# VOICE.net
KiCad netlist of a schematic drawn in Altium Designer
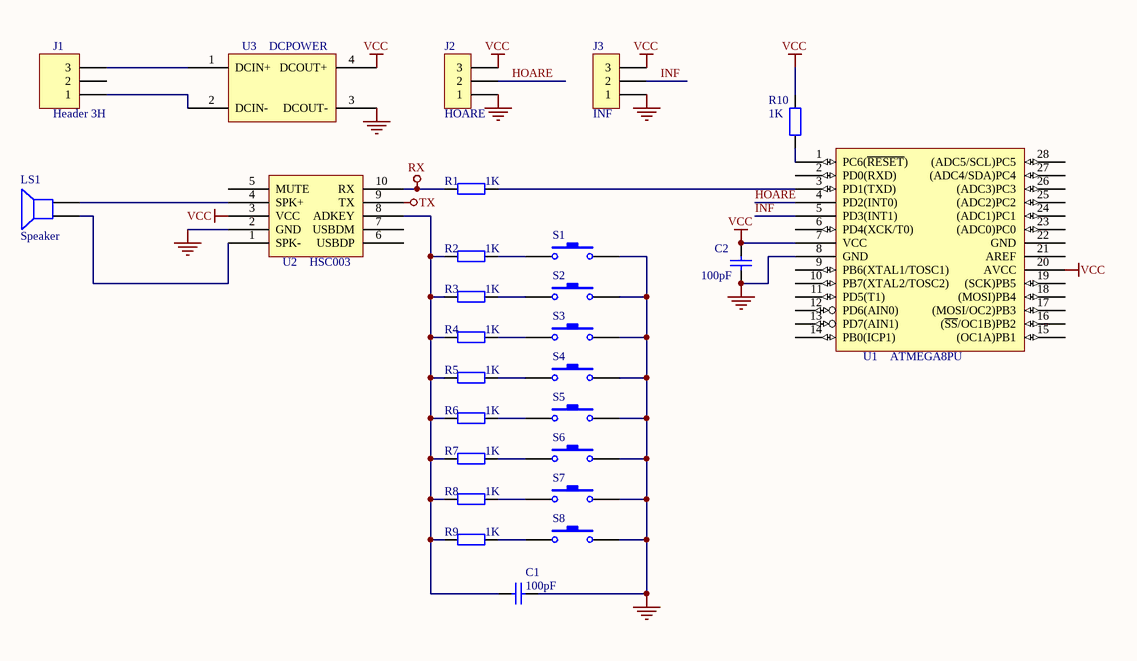
[diagram p0: VOICE.SchDoc]

(export (version "E")
  (design (tool "Eeschema 10.0.6"))
  (components
    (comp (ref "C1")
      (value "100pF")
      (footprint "RAD-0.3")
      (description "Capacitor")
      (fields (field (name "Comment") "CAP") (field (name "PUBLISHER") "Altium Limited"))
      (libsource (lib "Miscellaneous Devices") (part "Cap"))
    )
    (comp (ref "C2")
      (value "100pF")
      (footprint "RAD-0.3")
      (description "Capacitor")
      (fields (field (name "Comment") "CAP") (field (name "PUBLISHER") "Altium Limited"))
      (libsource (lib "Miscellaneous Devices") (part "Cap"))
    )
    (comp (ref "J1")
      (value "Header 3H")
      (footprint "HDR1X3H")
      (description "Header, 3-Pin, Right Angle")
      (fields (field (name "PUBLISHER") "Altium Limited"))
      (libsource (lib "Miscellaneous Connectors") (part "Header 3H"))
    )
    (comp (ref "J2") (value "HOARE") (description "Connector") (libsource (lib "*") (part "CON3")))
    (comp (ref "J3") (value "INF") (description "Connector") (libsource (lib "*") (part "CON3")))
    (comp (ref "LS1")
      (value "Speaker")
      (footprint "PIN2")
      (description "Loudspeaker")
      (fields (field (name "PUBLISHER") "Altium Limited"))
      (libsource (lib "Miscellaneous Devices") (part "Speaker"))
    )
    (comp (ref "R1")
      (value "1K")
      (footprint "AXIAL-0.4")
      (description "Resistor")
      (fields (field (name "Comment") "RES2") (field (name "PUBLISHER") "Altium Limited"))
      (libsource (lib "") (part "Res2_1"))
    )
    (comp (ref "R2")
      (value "1K")
      (footprint "AXIAL-0.4")
      (description "Resistor")
      (fields (field (name "Comment") "RES2") (field (name "PUBLISHER") "Altium Limited"))
      (libsource (lib "") (part "Res2_1"))
    )
    (comp (ref "R3")
      (value "1K")
      (footprint "AXIAL-0.4")
      (description "Resistor")
      (fields (field (name "Comment") "RES2") (field (name "PUBLISHER") "Altium Limited"))
      (libsource (lib "") (part "Res2_1"))
    )
    (comp (ref "R4")
      (value "1K")
      (footprint "AXIAL-0.4")
      (description "Resistor")
      (fields (field (name "Comment") "RES2") (field (name "PUBLISHER") "Altium Limited"))
      (libsource (lib "") (part "Res2_1"))
    )
    (comp (ref "R5")
      (value "1K")
      (footprint "AXIAL-0.4")
      (description "Resistor")
      (fields (field (name "Comment") "RES2") (field (name "PUBLISHER") "Altium Limited"))
      (libsource (lib "") (part "Res2_1"))
    )
    (comp (ref "R6")
      (value "1K")
      (footprint "AXIAL-0.4")
      (description "Resistor")
      (fields (field (name "Comment") "RES2") (field (name "PUBLISHER") "Altium Limited"))
      (libsource (lib "") (part "Res2_1"))
    )
    (comp (ref "R7")
      (value "1K")
      (footprint "AXIAL-0.4")
      (description "Resistor")
      (fields (field (name "Comment") "RES2") (field (name "PUBLISHER") "Altium Limited"))
      (libsource (lib "") (part "Res2_1"))
    )
    (comp (ref "R8")
      (value "1K")
      (footprint "AXIAL-0.4")
      (description "Resistor")
      (fields (field (name "Comment") "RES2") (field (name "PUBLISHER") "Altium Limited"))
      (libsource (lib "") (part "Res2_1"))
    )
    (comp (ref "R9")
      (value "1K")
      (footprint "AXIAL-0.4")
      (description "Resistor")
      (fields (field (name "Comment") "RES2") (field (name "PUBLISHER") "Altium Limited"))
      (libsource (lib "") (part "Res2_1"))
    )
    (comp (ref "R10")
      (value "1K")
      (footprint "AXIAL-0.4")
      (description "Resistor")
      (fields (field (name "Comment") "RES2") (field (name "PUBLISHER") "Altium Limited"))
      (libsource (lib "Miscellaneous Devices") (part "Res2"))
    )
    (comp (ref "S1")
      (value "SW-PB")
      (footprint "SPST-2")
      (description "Switch")
      (fields (field (name "PUBLISHER") "Altium Limited"))
      (libsource (lib "Miscellaneous Devices") (part "SW-PB"))
    )
    (comp (ref "S2")
      (value "SW-PB")
      (footprint "SPST-2")
      (description "Switch")
      (fields (field (name "PUBLISHER") "Altium Limited"))
      (libsource (lib "Miscellaneous Devices") (part "SW-PB"))
    )
    (comp (ref "S3")
      (value "SW-PB")
      (footprint "SPST-2")
      (description "Switch")
      (fields (field (name "PUBLISHER") "Altium Limited"))
      (libsource (lib "Miscellaneous Devices") (part "SW-PB"))
    )
    (comp (ref "S4")
      (value "SW-PB")
      (footprint "SPST-2")
      (description "Switch")
      (fields (field (name "PUBLISHER") "Altium Limited"))
      (libsource (lib "Miscellaneous Devices") (part "SW-PB"))
    )
    (comp (ref "S5")
      (value "SW-PB")
      (footprint "SPST-2")
      (description "Switch")
      (fields (field (name "PUBLISHER") "Altium Limited"))
      (libsource (lib "Miscellaneous Devices") (part "SW-PB"))
    )
    (comp (ref "S6")
      (value "SW-PB")
      (footprint "SPST-2")
      (description "Switch")
      (fields (field (name "PUBLISHER") "Altium Limited"))
      (libsource (lib "Miscellaneous Devices") (part "SW-PB"))
    )
    (comp (ref "S7")
      (value "SW-PB")
      (footprint "SPST-2")
      (description "Switch")
      (fields (field (name "PUBLISHER") "Altium Limited"))
      (libsource (lib "Miscellaneous Devices") (part "SW-PB"))
    )
    (comp (ref "S8")
      (value "SW-PB")
      (footprint "SPST-2")
      (description "Switch")
      (fields (field (name "PUBLISHER") "Altium Limited"))
      (libsource (lib "Miscellaneous Devices") (part "SW-PB"))
    )
    (comp (ref "U1") (value "ATMEGA8PU") (libsource (lib "voice") (part "ATMEGA8PU")))
    (comp (ref "U2") (value "HSC003") (libsource (lib "voice") (part "HSC003")))
    (comp (ref "U3") (value "DCPOWER") (libsource (lib "voice") (part "DCPOWER")))
  )
  (nets
    (net (code "1") (name "/HOARE") (class "Default")
      (node (ref "J2") (pin "2") (pinfunction "2_2") (pintype "passive"))
      (node (ref "U1") (pin "4") (pinfunction "PD2(INT0)_4") (pintype "passive"))
    )
    (net (code "2") (name "/INF") (class "Default")
      (node (ref "J3") (pin "2") (pinfunction "2_2") (pintype "passive"))
      (node (ref "U1") (pin "5") (pinfunction "PD3(INT1)_5") (pintype "passive"))
    )
    (net (code "3") (name "Net-(R2-Pad2)") (class "Default")
      (node (ref "R2") (pin "2") (pinfunction "2_2") (pintype "passive"))
      (node (ref "S1") (pin "1") (pinfunction "1_1") (pintype "passive"))
    )
    (net (code "4") (name "Net-(R3-Pad2)") (class "Default")
      (node (ref "R3") (pin "2") (pinfunction "2_2") (pintype "passive"))
      (node (ref "S2") (pin "1") (pinfunction "1_1") (pintype "passive"))
    )
    (net (code "5") (name "Net-(R4-Pad2)") (class "Default")
      (node (ref "R4") (pin "2") (pinfunction "2_2") (pintype "passive"))
      (node (ref "S3") (pin "1") (pinfunction "1_1") (pintype "passive"))
    )
    (net (code "6") (name "Net-(R5-Pad2)") (class "Default")
      (node (ref "R5") (pin "2") (pinfunction "2_2") (pintype "passive"))
      (node (ref "S4") (pin "1") (pinfunction "1_1") (pintype "passive"))
    )
    (net (code "7") (name "Net-(R6-Pad2)") (class "Default")
      (node (ref "R6") (pin "2") (pinfunction "2_2") (pintype "passive"))
      (node (ref "S5") (pin "1") (pinfunction "1_1") (pintype "passive"))
    )
    (net (code "8") (name "Net-(R7-Pad2)") (class "Default")
      (node (ref "R7") (pin "2") (pinfunction "2_2") (pintype "passive"))
      (node (ref "S6") (pin "1") (pinfunction "1_1") (pintype "passive"))
    )
    (net (code "9") (name "Net-(R8-Pad2)") (class "Default")
      (node (ref "R8") (pin "2") (pinfunction "2_2") (pintype "passive"))
      (node (ref "S7") (pin "1") (pinfunction "1_1") (pintype "passive"))
    )
    (net (code "10") (name "Net-(R9-Pad2)") (class "Default")
      (node (ref "R9") (pin "2") (pinfunction "2_2") (pintype "passive"))
      (node (ref "S8") (pin "1") (pinfunction "1_1") (pintype "passive"))
    )
    (net (code "11") (name "Net-(U1-PC6(~{RESET}))") (class "Default")
      (node (ref "R10") (pin "1") (pinfunction "1_1") (pintype "passive"))
      (node (ref "U1") (pin "1") (pinfunction "PC6(~{RESET})_1") (pintype "bidirectional"))
    )
    (net (code "12") (name "Net-(U1-PD1(TXD))") (class "Default")
      (node (ref "R1") (pin "2") (pinfunction "2_2") (pintype "passive"))
      (node (ref "U1") (pin "3") (pinfunction "PD1(TXD)_3") (pintype "bidirectional"))
    )
    (net (code "13") (name "Net-(U2-ADKEY)") (class "Default")
      (node (ref "C1") (pin "2") (pinfunction "2_2") (pintype "passive"))
      (node (ref "R2") (pin "1") (pinfunction "1_1") (pintype "passive"))
      (node (ref "R3") (pin "1") (pinfunction "1_1") (pintype "passive"))
      (node (ref "R4") (pin "1") (pinfunction "1_1") (pintype "passive"))
      (node (ref "R5") (pin "1") (pinfunction "1_1") (pintype "passive"))
      (node (ref "R6") (pin "1") (pinfunction "1_1") (pintype "passive"))
      (node (ref "R7") (pin "1") (pinfunction "1_1") (pintype "passive"))
      (node (ref "R8") (pin "1") (pinfunction "1_1") (pintype "passive"))
      (node (ref "R9") (pin "1") (pinfunction "1_1") (pintype "passive"))
      (node (ref "U2") (pin "8") (pinfunction "ADKEY_8") (pintype "passive"))
    )
    (net (code "14") (name "Net-(U2-SPK+)") (class "Default")
      (node (ref "LS1") (pin "2") (pinfunction "2_2") (pintype "passive"))
      (node (ref "U2") (pin "4") (pinfunction "SPK+_4") (pintype "passive"))
    )
    (net (code "15") (name "Net-(U2-SPK-)") (class "Default")
      (node (ref "LS1") (pin "1") (pinfunction "1_1") (pintype "passive"))
      (node (ref "U2") (pin "1") (pinfunction "SPK-_1") (pintype "passive"))
    )
    (net (code "16") (name "Net-(U3-DCIN+)") (class "Default")
      (node (ref "J1") (pin "3") (pinfunction "3_3") (pintype "passive"))
      (node (ref "U3") (pin "1") (pinfunction "DCIN+_1") (pintype "power_in"))
    )
    (net (code "17") (name "Net-(U3-DCIN-)") (class "Default")
      (node (ref "J1") (pin "1") (pinfunction "1_1") (pintype "passive"))
      (node (ref "U3") (pin "2") (pinfunction "DCIN-_2") (pintype "power_in"))
    )
    (net (code "18") (name "RX") (class "Default")
      (node (ref "R1") (pin "1") (pinfunction "1_1") (pintype "passive"))
      (node (ref "U2") (pin "10") (pinfunction "RX_10") (pintype "passive"))
    )
    (net (code "19") (name "TX") (class "Default")
      (node (ref "U2") (pin "9") (pinfunction "TX_9") (pintype "passive"))
    )
    (net (code "20") (name "VCC") (class "Default")
      (node (ref "C1") (pin "1") (pinfunction "1_1") (pintype "passive"))
      (node (ref "C2") (pin "1") (pinfunction "1_1") (pintype "passive"))
      (node (ref "C2") (pin "2") (pinfunction "2_2") (pintype "passive"))
      (node (ref "J2") (pin "1") (pinfunction "1_1") (pintype "passive"))
      (node (ref "J2") (pin "3") (pinfunction "3_3") (pintype "passive"))
      (node (ref "J3") (pin "1") (pinfunction "1_1") (pintype "passive"))
      (node (ref "J3") (pin "3") (pinfunction "3_3") (pintype "passive"))
      (node (ref "R10") (pin "2") (pinfunction "2_2") (pintype "passive"))
      (node (ref "S1") (pin "2") (pinfunction "2_2") (pintype "passive"))
      (node (ref "S2") (pin "2") (pinfunction "2_2") (pintype "passive"))
      (node (ref "S3") (pin "2") (pinfunction "2_2") (pintype "passive"))
      (node (ref "S4") (pin "2") (pinfunction "2_2") (pintype "passive"))
      (node (ref "S5") (pin "2") (pinfunction "2_2") (pintype "passive"))
      (node (ref "S6") (pin "2") (pinfunction "2_2") (pintype "passive"))
      (node (ref "S7") (pin "2") (pinfunction "2_2") (pintype "passive"))
      (node (ref "S8") (pin "2") (pinfunction "2_2") (pintype "passive"))
      (node (ref "U1") (pin "20") (pinfunction "AVCC_20") (pintype "power_in"))
      (node (ref "U1") (pin "7") (pinfunction "VCC_7") (pintype "power_in"))
      (node (ref "U1") (pin "8") (pinfunction "GND_8") (pintype "power_in"))
      (node (ref "U2") (pin "2") (pinfunction "GND_2") (pintype "power_in"))
      (node (ref "U2") (pin "3") (pinfunction "VCC_3") (pintype "power_in"))
      (node (ref "U3") (pin "3") (pinfunction "DCOUT-_3") (pintype "power_in"))
      (node (ref "U3") (pin "4") (pinfunction "DCOUT+_4") (pintype "power_in"))
    )
    (net (code "21") (name "unconnected-(J1-Pad2)") (class "Default")
      (node (ref "J1") (pin "2") (pinfunction "2_2") (pintype "passive"))
    )
    (net (code "22") (name "unconnected-(U1-(ADC0)PC0-Pad23)") (class "Default")
      (node (ref "U1") (pin "23") (pinfunction "(ADC0)PC0_23") (pintype "bidirectional"))
    )
    (net (code "23") (name "unconnected-(U1-(ADC1)PC1-Pad24)") (class "Default")
      (node (ref "U1") (pin "24") (pinfunction "(ADC1)PC1_24") (pintype "bidirectional"))
    )
    (net (code "24") (name "unconnected-(U1-(ADC2)PC2-Pad25)") (class "Default")
      (node (ref "U1") (pin "25") (pinfunction "(ADC2)PC2_25") (pintype "bidirectional"))
    )
    (net (code "25") (name "unconnected-(U1-(ADC3)PC3-Pad26)") (class "Default")
      (node (ref "U1") (pin "26") (pinfunction "(ADC3)PC3_26") (pintype "bidirectional"))
    )
    (net (code "26") (name "unconnected-(U1-(ADC4{slash}SDA)PC4-Pad27)") (class "Default")
      (node (ref "U1") (pin "27") (pinfunction "(ADC4/SDA)PC4_27") (pintype "bidirectional"))
    )
    (net (code "27") (name "unconnected-(U1-(ADC5{slash}SCL)PC5-Pad28)") (class "Default")
      (node (ref "U1") (pin "28") (pinfunction "(ADC5/SCL)PC5_28") (pintype "bidirectional"))
    )
    (net (code "28") (name "unconnected-(U1-(MOSI)PB4-Pad18)") (class "Default")
      (node (ref "U1") (pin "18") (pinfunction "(MOSI)PB4_18") (pintype "bidirectional"))
    )
    (net (code "29") (name "unconnected-(U1-(MOSI{slash}OC2)PB3-Pad17)") (class "Default")
      (node (ref "U1") (pin "17") (pinfunction "(MOSI/OC2)PB3_17") (pintype "bidirectional"))
    )
    (net (code "30") (name "unconnected-(U1-(OC1A)PB1-Pad15)") (class "Default")
      (node (ref "U1") (pin "15") (pinfunction "(OC1A)PB1_15") (pintype "bidirectional"))
    )
    (net (code "31") (name "unconnected-(U1-(SCK)PB5-Pad19)") (class "Default")
      (node (ref "U1") (pin "19") (pinfunction "(SCK)PB5_19") (pintype "bidirectional"))
    )
    (net (code "32") (name "unconnected-(U1-(~{SS}{slash}OC1B)PB2-Pad16)") (class "Default")
      (node (ref "U1") (pin "16") (pinfunction "(~{SS}/OC1B)PB2_16") (pintype "bidirectional"))
    )
    (net (code "33") (name "unconnected-(U1-AREF-Pad21)") (class "Default")
      (node (ref "U1") (pin "21") (pinfunction "AREF_21") (pintype "passive"))
    )
    (net (code "34") (name "unconnected-(U1-GND-Pad22)") (class "Default")
      (node (ref "U1") (pin "22") (pinfunction "GND_22") (pintype "power_in"))
    )
    (net (code "35") (name "unconnected-(U1-PB0(ICP1)-Pad14)") (class "Default")
      (node (ref "U1") (pin "14") (pinfunction "PB0(ICP1)_14") (pintype "bidirectional"))
    )
    (net (code "36") (name "unconnected-(U1-PB6(XTAL1{slash}TOSC1)-Pad9)") (class "Default")
      (node (ref "U1") (pin "9") (pinfunction "PB6(XTAL1/TOSC1)_9") (pintype "bidirectional"))
    )
    (net (code "37") (name "unconnected-(U1-PB7(XTAL2{slash}TOSC2)-Pad10)") (class "Default")
      (node (ref "U1") (pin "10") (pinfunction "PB7(XTAL2/TOSC2)_10") (pintype "bidirectional"))
    )
    (net (code "38") (name "unconnected-(U1-PD0(RXD)-Pad2)") (class "Default")
      (node (ref "U1") (pin "2") (pinfunction "PD0(RXD)_2") (pintype "bidirectional"))
    )
    (net (code "39") (name "unconnected-(U1-PD4(XCK{slash}T0)-Pad6)") (class "Default")
      (node (ref "U1") (pin "6") (pinfunction "PD4(XCK/T0)_6") (pintype "bidirectional"))
    )
    (net (code "40") (name "unconnected-(U1-PD5(T1)-Pad11)") (class "Default")
      (node (ref "U1") (pin "11") (pinfunction "PD5(T1)_11") (pintype "bidirectional"))
    )
    (net (code "41") (name "unconnected-(U1-PD6(AIN0)-Pad12)") (class "Default")
      (node (ref "U1") (pin "12") (pinfunction "PD6(AIN0)_12") (pintype "bidirectional"))
    )
    (net (code "42") (name "unconnected-(U1-PD7(AIN1)-Pad13)") (class "Default")
      (node (ref "U1") (pin "13") (pinfunction "PD7(AIN1)_13") (pintype "bidirectional"))
    )
    (net (code "43") (name "unconnected-(U2-MUTE-Pad5)") (class "Default")
      (node (ref "U2") (pin "5") (pinfunction "MUTE_5") (pintype "passive"))
    )
    (net (code "44") (name "unconnected-(U2-USBDM-Pad7)") (class "Default")
      (node (ref "U2") (pin "7") (pinfunction "USBDM_7") (pintype "passive"))
    )
    (net (code "45") (name "unconnected-(U2-USBDP-Pad6)") (class "Default")
      (node (ref "U2") (pin "6") (pinfunction "USBDP_6") (pintype "passive"))
    )
  )
)
